# USB-Serial-IO-MCP2221.net
KiCad netlist of a schematic drawn in EasyEDA
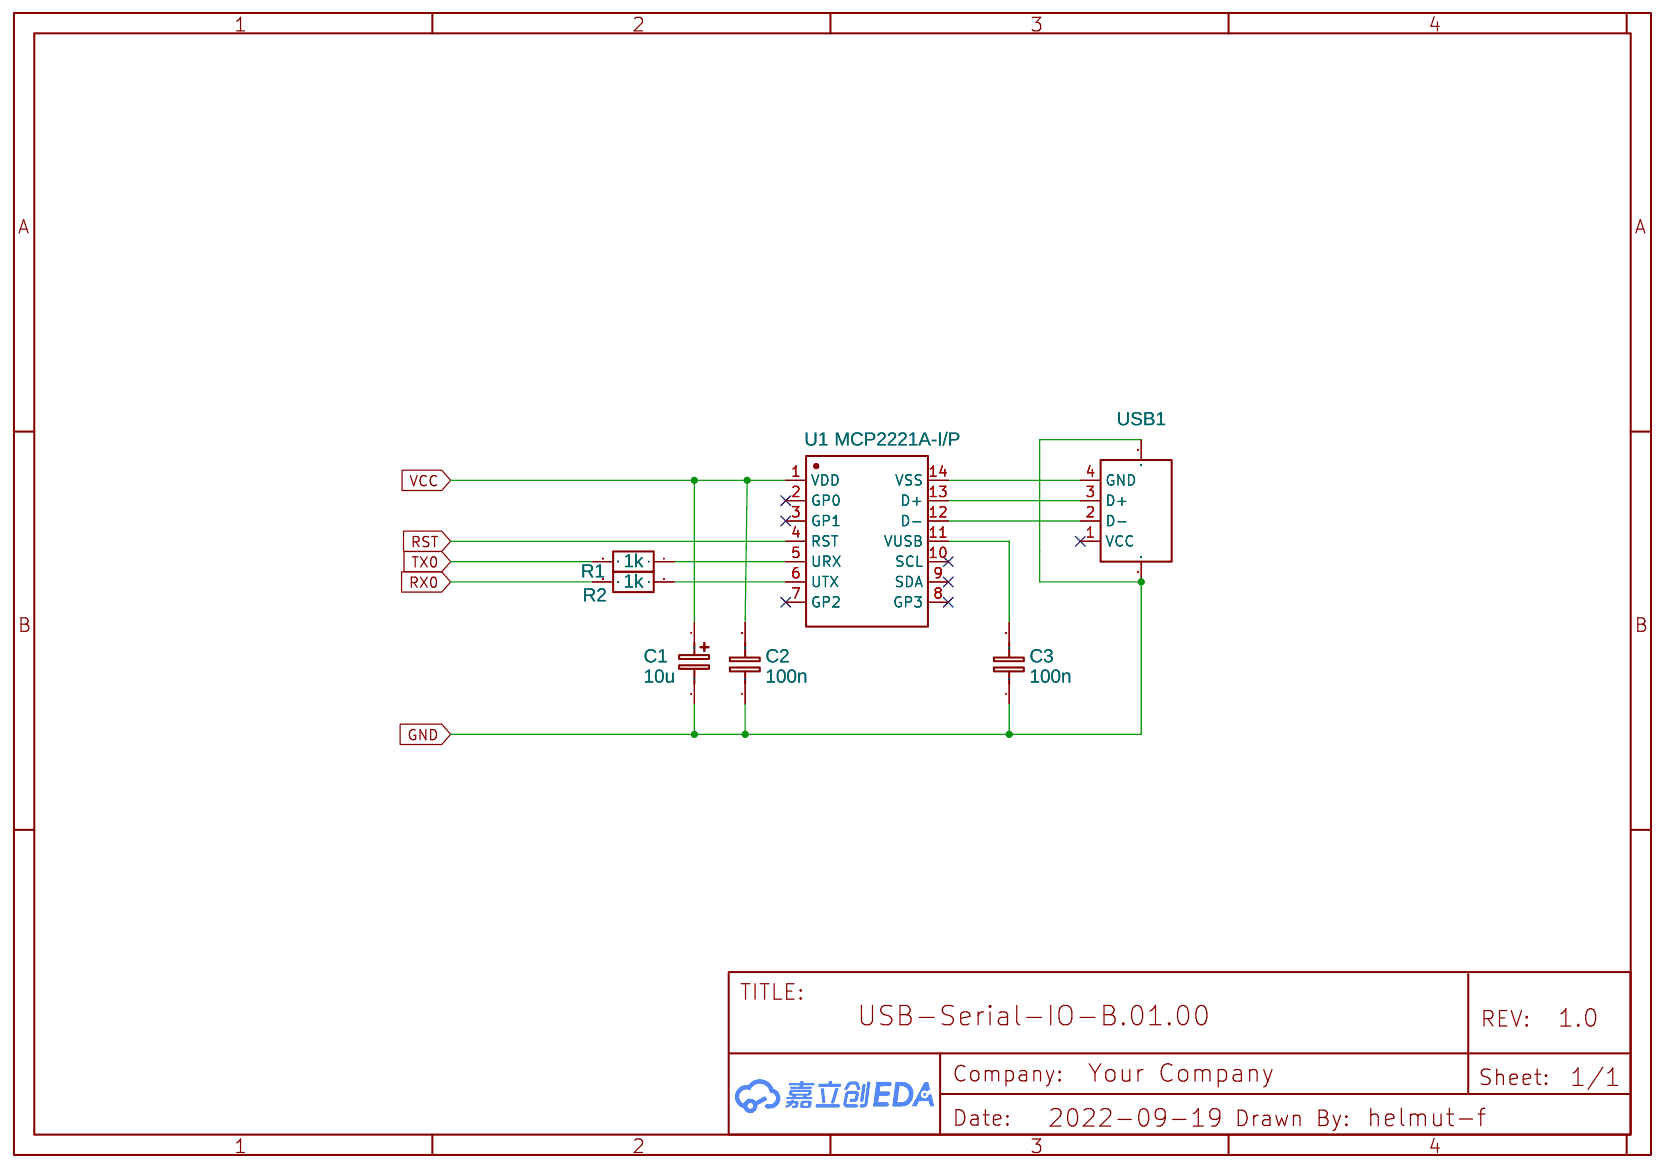
[diagram p0: schematic sheet]

(export (version "E")
  (design (tool "Eeschema 10.0.6"))
  (components
    (comp (ref "C1") (value "10u") (libsource (lib "") (part "CE_TH_D4.0×F1.5_EU")))
    (comp (ref "C2") (value "100n") (libsource (lib "") (part "C_0603_EU")))
    (comp (ref "C3") (value "100n") (libsource (lib "") (part "C_0603_EU")))
    (comp (ref "R1") (value "1k") (libsource (lib "") (part "R_AXIAL-0.3_EU")))
    (comp (ref "R2") (value "1k") (libsource (lib "") (part "R_AXIAL-0.3_EU")))
    (comp (ref "U1") (value "MCP2221A-I/P") (libsource (lib "") (part "MCP2221A-I/P")))
    (comp (ref "USB1")
      (value "USB-Type A_Male")
      (fields (field (name "Manufacturer Part") "USB-05") (field (name "Manufacturer") "SOFNG"))
      (libsource (lib "") (part "USB-Type A_Male"))
    )
  )
  (nets
    (net (code "1") (name "GND") (class "Default")
      (node (ref "C1") (pin "2") (pinfunction "2_2") (pintype "unspecified"))
      (node (ref "C2") (pin "1") (pinfunction "1_1") (pintype "unspecified"))
      (node (ref "C3") (pin "1") (pinfunction "1_1") (pintype "unspecified"))
      (node (ref "USB1") (pin "5") (pinfunction "5_5") (pintype "unspecified"))
      (node (ref "USB1") (pin "6") (pinfunction "6_6") (pintype "unspecified"))
    )
    (net (code "2") (name "Net-(U1-D+)") (class "Default")
      (node (ref "U1") (pin "13") (pinfunction "D+_13") (pintype "unspecified"))
      (node (ref "USB1") (pin "3") (pinfunction "D+_3") (pintype "input"))
    )
    (net (code "3") (name "Net-(U1-D-)") (class "Default")
      (node (ref "U1") (pin "12") (pinfunction "D-_12") (pintype "unspecified"))
      (node (ref "USB1") (pin "2") (pinfunction "D-_2") (pintype "input"))
    )
    (net (code "4") (name "Net-(U1-URX)") (class "Default")
      (node (ref "R1") (pin "1") (pinfunction "1_1") (pintype "unspecified"))
      (node (ref "U1") (pin "5") (pinfunction "URX_5") (pintype "unspecified"))
    )
    (net (code "5") (name "Net-(U1-UTX)") (class "Default")
      (node (ref "R2") (pin "1") (pinfunction "1_1") (pintype "unspecified"))
      (node (ref "U1") (pin "6") (pinfunction "UTX_6") (pintype "unspecified"))
    )
    (net (code "6") (name "Net-(U1-VSS)") (class "Default")
      (node (ref "U1") (pin "14") (pinfunction "VSS_14") (pintype "unspecified"))
      (node (ref "USB1") (pin "4") (pinfunction "GND_4") (pintype "input"))
    )
    (net (code "7") (name "Net-(U1-VUSB)") (class "Default")
      (node (ref "C3") (pin "2") (pinfunction "2_2") (pintype "unspecified"))
      (node (ref "U1") (pin "11") (pinfunction "VUSB_11") (pintype "unspecified"))
    )
    (net (code "8") (name "RST") (class "Default")
      (node (ref "U1") (pin "4") (pinfunction "RST_4") (pintype "unspecified"))
    )
    (net (code "9") (name "RX0") (class "Default")
      (node (ref "R2") (pin "2") (pinfunction "2_2") (pintype "unspecified"))
    )
    (net (code "10") (name "TX0") (class "Default")
      (node (ref "R1") (pin "2") (pinfunction "2_2") (pintype "unspecified"))
    )
    (net (code "11") (name "VCC") (class "Default")
      (node (ref "C1") (pin "1") (pinfunction "1_1") (pintype "unspecified"))
      (node (ref "C2") (pin "2") (pinfunction "2_2") (pintype "unspecified"))
      (node (ref "U1") (pin "1") (pinfunction "VDD_1") (pintype "unspecified"))
    )
    (net (code "12") (name "unconnected-(U1-GP0-Pad2)") (class "Default")
      (node (ref "U1") (pin "2") (pinfunction "GP0_2") (pintype "unspecified+no_connect"))
    )
    (net (code "13") (name "unconnected-(U1-GP1-Pad3)") (class "Default")
      (node (ref "U1") (pin "3") (pinfunction "GP1_3") (pintype "unspecified+no_connect"))
    )
    (net (code "14") (name "unconnected-(U1-GP2-Pad7)") (class "Default")
      (node (ref "U1") (pin "7") (pinfunction "GP2_7") (pintype "unspecified+no_connect"))
    )
    (net (code "15") (name "unconnected-(U1-GP3-Pad8)") (class "Default")
      (node (ref "U1") (pin "8") (pinfunction "GP3_8") (pintype "unspecified+no_connect"))
    )
    (net (code "16") (name "unconnected-(U1-SCL-Pad10)") (class "Default")
      (node (ref "U1") (pin "10") (pinfunction "SCL_10") (pintype "unspecified+no_connect"))
    )
    (net (code "17") (name "unconnected-(U1-SDA-Pad9)") (class "Default")
      (node (ref "U1") (pin "9") (pinfunction "SDA_9") (pintype "unspecified+no_connect"))
    )
    (net (code "18") (name "unconnected-(USB1-VCC-Pad1)") (class "Default")
      (node (ref "USB1") (pin "1") (pinfunction "VCC_1") (pintype "input+no_connect"))
    )
  )
)
